# Adapter_boardV1.net
KiCad netlist of a schematic drawn in EAGLE
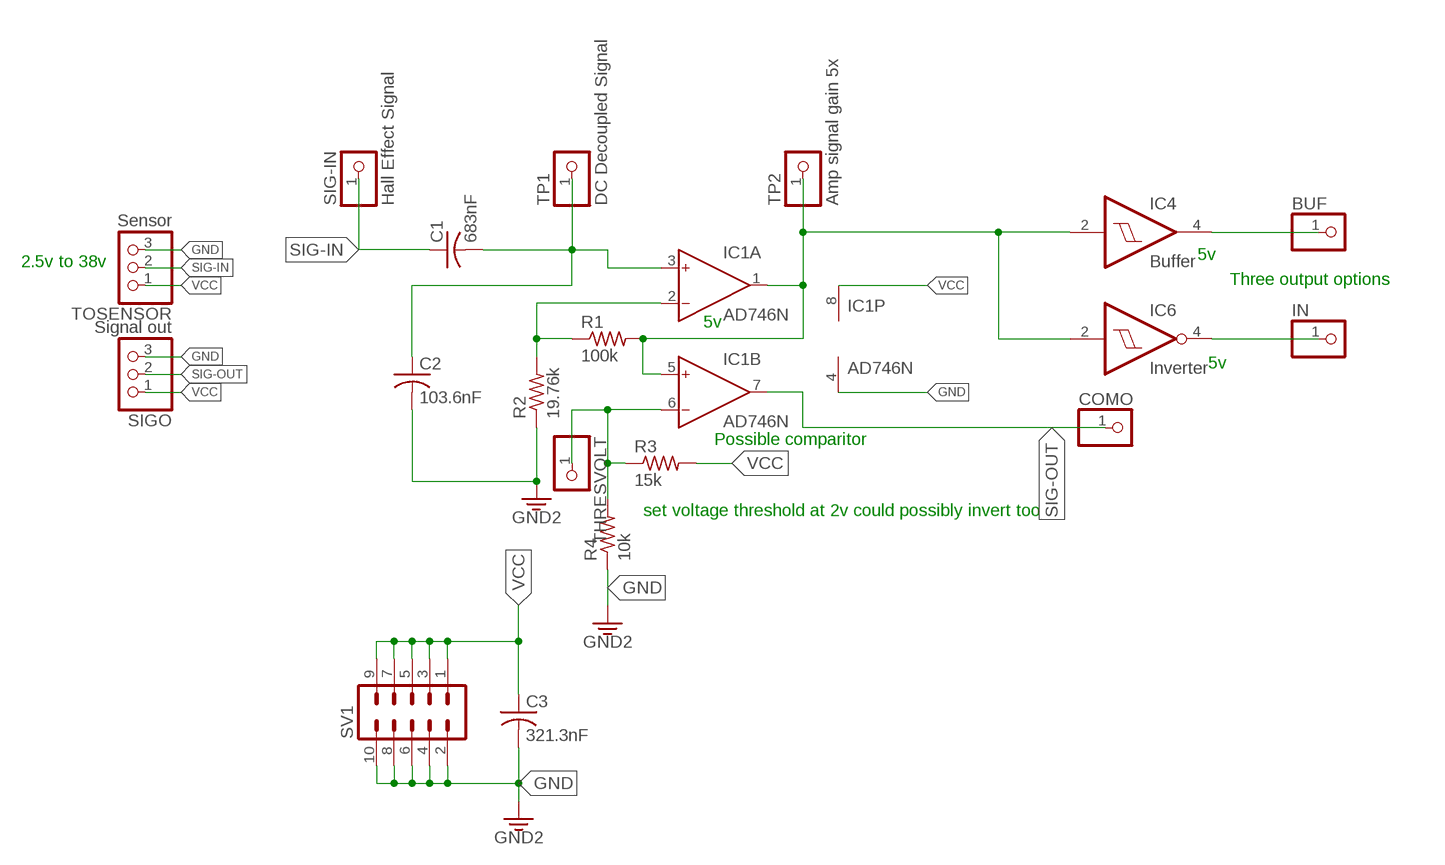
[diagram p0: schematic, sheet 1]

(export (version "E")
  (design (tool "Eeschema 10.0.6"))
  (components
    (comp (ref "BUF")
      (value "PINHD-1X1")
      (footprint "eagle-import:1X01")
      (libsource (lib "eagle-import") (part "PINHD-1X1"))
    )
    (comp (ref "C1")
      (value "683nF")
      (footprint "eagle-import:C0805")
      (libsource (lib "eagle-import") (part "C-USC0805"))
    )
    (comp (ref "C2")
      (value "103.6nF")
      (footprint "eagle-import:C0805")
      (libsource (lib "eagle-import") (part "C-USC0805"))
    )
    (comp (ref "C3")
      (value "321.3nF")
      (footprint "eagle-import:C0805")
      (libsource (lib "eagle-import") (part "C-USC0805"))
    )
    (comp (ref "COMO")
      (value "PINHD-1X1")
      (footprint "eagle-import:1X01")
      (libsource (lib "eagle-import") (part "PINHD-1X1"))
    )
    (comp (ref "IC1")
      (value "AD746N")
      (footprint "eagle-import:DIL08")
      (fields (field (name "MF") "ALTERA CORPORATION") (field (name "MPN") "AD746JNZ"))
      (libsource (lib "eagle-import") (part "AD746N"))
    )
    (comp (ref "IC4")
      (value "Buffer")
      (footprint "eagle-import:SOT23-5")
      (libsource (lib "eagle-import") (part "741G17DBVLVC"))
    )
    (comp (ref "IC6")
      (value "Inverter")
      (footprint "eagle-import:SOT23-5")
      (libsource (lib "eagle-import") (part "741G14DBVLVC"))
    )
    (comp (ref "IN")
      (value "PINHD-1X1")
      (footprint "eagle-import:1X01")
      (libsource (lib "eagle-import") (part "PINHD-1X1"))
    )
    (comp (ref "R1")
      (value "100k")
      (footprint "eagle-import:0805-THM-7")
      (libsource (lib "eagle-import") (part "R-US_FLIPFLOP7"))
    )
    (comp (ref "R2")
      (value "19.76k")
      (footprint "eagle-import:0805-THM-7")
      (libsource (lib "eagle-import") (part "R-US_FLIPFLOP7"))
    )
    (comp (ref "R3")
      (value "15k")
      (footprint "eagle-import:0805-THM-7")
      (libsource (lib "eagle-import") (part "R-US_FLIPFLOP7"))
    )
    (comp (ref "R4")
      (value "10k")
      (footprint "eagle-import:0805-THM-7")
      (libsource (lib "eagle-import") (part "R-US_FLIPFLOP7"))
    )
    (comp (ref "SIG-IN")
      (value "Hall Effect Signal")
      (footprint "eagle-import:1X01")
      (libsource (lib "eagle-import") (part "PINHD-1X1"))
    )
    (comp (ref "SIGO")
      (value "Signal out")
      (footprint "eagle-import:1X03")
      (libsource (lib "eagle-import") (part "PINHD-1X3"))
    )
    (comp (ref "SV1")
      (value "MA05-2")
      (footprint "eagle-import:MA05-2")
      (libsource (lib "eagle-import") (part "MA05-2"))
    )
    (comp (ref "THRESVOLT")
      (value "PINHD-1X1")
      (footprint "eagle-import:1X01")
      (libsource (lib "eagle-import") (part "PINHD-1X1"))
    )
    (comp (ref "TOSENSOR")
      (value "Sensor")
      (footprint "eagle-import:1X03")
      (libsource (lib "eagle-import") (part "PINHD-1X3"))
    )
    (comp (ref "TP1")
      (value "DC Decoupled Signal")
      (footprint "eagle-import:1X01")
      (libsource (lib "eagle-import") (part "PINHD-1X1"))
    )
    (comp (ref "TP2")
      (value "Amp signal gain 5x")
      (footprint "eagle-import:1X01")
      (libsource (lib "eagle-import") (part "PINHD-1X1"))
    )
  )
  (nets
    (net (code "1") (name "GND") (class "Default")
      (node (ref "C2") (pin "2") (pinfunction "2_2") (pintype "passive"))
      (node (ref "C3") (pin "2") (pinfunction "2_2") (pintype "passive"))
      (node (ref "IC1") (pin "4") (pinfunction "V-_4") (pintype "power_in"))
      (node (ref "R2") (pin "1") (pinfunction "1_1") (pintype "passive"))
      (node (ref "R4") (pin "1") (pinfunction "1_1") (pintype "passive"))
      (node (ref "SIGO") (pin "3") (pinfunction "3_3") (pintype "passive"))
      (node (ref "SV1") (pin "10") (pinfunction "10_10") (pintype "passive"))
      (node (ref "SV1") (pin "2") (pinfunction "2_2") (pintype "passive"))
      (node (ref "SV1") (pin "4") (pinfunction "4_4") (pintype "passive"))
      (node (ref "SV1") (pin "6") (pinfunction "6_6") (pintype "passive"))
      (node (ref "SV1") (pin "8") (pinfunction "8_8") (pintype "passive"))
      (node (ref "TOSENSOR") (pin "3") (pinfunction "3_3") (pintype "passive"))
    )
    (net (code "2") (name "Net-(IC1A-IN+)") (class "Default")
      (node (ref "C1") (pin "2") (pinfunction "2_2") (pintype "passive"))
      (node (ref "C2") (pin "1") (pinfunction "1_1") (pintype "passive"))
      (node (ref "IC1") (pin "3") (pinfunction "IN+_3") (pintype "input"))
      (node (ref "TP1") (pin "1") (pinfunction "1_1") (pintype "passive"))
    )
    (net (code "3") (name "Net-(IC1A-IN-)") (class "Default")
      (node (ref "IC1") (pin "2") (pinfunction "IN-_2") (pintype "input"))
      (node (ref "R1") (pin "1") (pinfunction "1_1") (pintype "passive"))
      (node (ref "R2") (pin "2") (pinfunction "2_2") (pintype "passive"))
    )
    (net (code "4") (name "Net-(IC1A-OUT)") (class "Default")
      (node (ref "IC1") (pin "1") (pinfunction "OUT_1") (pintype "output"))
      (node (ref "IC1") (pin "5") (pinfunction "IN+_5") (pintype "input"))
      (node (ref "IC4") (pin "2") (pinfunction "I_2") (pintype "input"))
      (node (ref "IC6") (pin "2") (pinfunction "I_2") (pintype "input"))
      (node (ref "R1") (pin "2") (pinfunction "2_2") (pintype "passive"))
      (node (ref "TP2") (pin "1") (pinfunction "1_1") (pintype "passive"))
    )
    (net (code "5") (name "Net-(IC1B-IN-)") (class "Default")
      (node (ref "IC1") (pin "6") (pinfunction "IN-_6") (pintype "input"))
      (node (ref "R3") (pin "1") (pinfunction "1_1") (pintype "passive"))
      (node (ref "R4") (pin "2") (pinfunction "2_2") (pintype "passive"))
      (node (ref "THRESVOLT") (pin "1") (pinfunction "1_1") (pintype "passive"))
    )
    (net (code "6") (name "Net-(IC4A-O)") (class "Default")
      (node (ref "BUF") (pin "1") (pinfunction "1_1") (pintype "passive"))
      (node (ref "IC4") (pin "4") (pinfunction "O_4") (pintype "output"))
    )
    (net (code "7") (name "Net-(IC6A-O)") (class "Default")
      (node (ref "IC6") (pin "4") (pinfunction "O_4") (pintype "output"))
      (node (ref "IN") (pin "1") (pinfunction "1_1") (pintype "passive"))
    )
    (net (code "8") (name "SIG-IN") (class "Default")
      (node (ref "C1") (pin "1") (pinfunction "1_1") (pintype "passive"))
      (node (ref "SIG-IN") (pin "1") (pinfunction "1_1") (pintype "passive"))
      (node (ref "TOSENSOR") (pin "2") (pinfunction "2_2") (pintype "passive"))
    )
    (net (code "9") (name "SIG-OUT") (class "Default")
      (node (ref "COMO") (pin "1") (pinfunction "1_1") (pintype "passive"))
      (node (ref "IC1") (pin "7") (pinfunction "OUT_7") (pintype "output"))
      (node (ref "SIGO") (pin "2") (pinfunction "2_2") (pintype "passive"))
    )
    (net (code "10") (name "VCC") (class "Default")
      (node (ref "C3") (pin "1") (pinfunction "1_1") (pintype "passive"))
      (node (ref "IC1") (pin "8") (pinfunction "V+_8") (pintype "power_in"))
      (node (ref "R3") (pin "2") (pinfunction "2_2") (pintype "passive"))
      (node (ref "SIGO") (pin "1") (pinfunction "1_1") (pintype "passive"))
      (node (ref "SV1") (pin "1") (pinfunction "1_1") (pintype "passive"))
      (node (ref "SV1") (pin "3") (pinfunction "3_3") (pintype "passive"))
      (node (ref "SV1") (pin "5") (pinfunction "5_5") (pintype "passive"))
      (node (ref "SV1") (pin "7") (pinfunction "7_7") (pintype "passive"))
      (node (ref "SV1") (pin "9") (pinfunction "9_9") (pintype "passive"))
      (node (ref "TOSENSOR") (pin "1") (pinfunction "1_1") (pintype "passive"))
    )
  )
)
